# reverse_pol_protection.net
KiCad netlist of a schematic drawn in Altium Designer
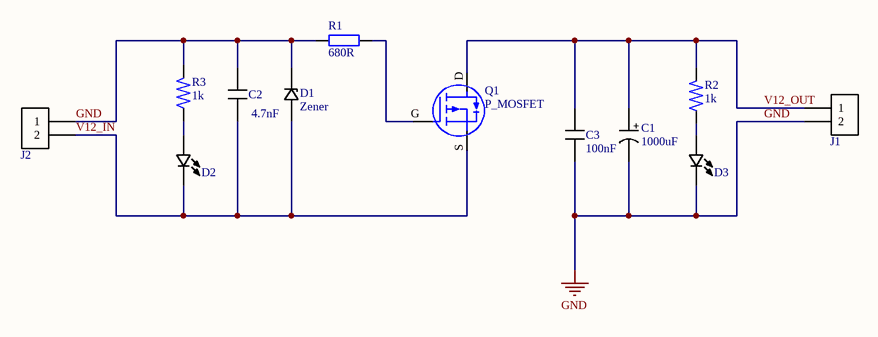
[diagram p0: reverse_pol_protection.SchDoc]

(export (version "E")
  (design (tool "Eeschema 10.0.6"))
  (components
    (comp (ref "C1")
      (value "1000uF")
      (footprint "RUBYCON_CAP_12.5x25")
      (description "Generic Electrolytic Capacitor")
      (libsource (lib "schematic_library") (part "Cap_Elec"))
    )
    (comp (ref "C2")
      (value "4.7nF")
      (footprint "YAGEO_CAP_0805_EA")
      (description "Generic Ceramic Capacitor")
      (libsource (lib "schematic_library") (part "Cap_Ceramic"))
    )
    (comp (ref "C3")
      (value "100nF")
      (footprint "YAGEO_CAP_0805_E0")
      (description "Generic Ceramic Capacitor")
      (libsource (lib "schematic_library") (part "Cap_Ceramic"))
    )
    (comp (ref "D1")
      (value "Zener")
      (footprint "NEXPERIA_DO-41")
      (description "Generic Zener Diode")
      (libsource (lib "intergrated_library") (part "Zener"))
    )
    (comp (ref "D2")
      (value "LED")
      (footprint "KINGBRIGHT_LED_THT_H4.9")
      (description "Generic Light Emitting Diode, Circuit indication")
      (libsource (lib "intergrated_library") (part "LED"))
    )
    (comp (ref "D3")
      (value "LED")
      (footprint "KINGBRIGHT_LED_THT_H4.9")
      (description "Generic Light Emitting Diode, Circuit indication")
      (libsource (lib "intergrated_library") (part "LED"))
    )
    (comp (ref "J1")
      (value "?")
      (footprint "KEFA_TERMINAL_2POS")
      (description "Generic 2 position terminal block")
      (libsource (lib "intergrated_library") (part "Terminal Block"))
    )
    (comp (ref "J2")
      (value "?")
      (footprint "KEFA_TERMINAL_2POS")
      (description "Generic 2 position terminal block")
      (libsource (lib "intergrated_library") (part "Terminal Block"))
    )
    (comp (ref "Q1")
      (value "P_MOSFET")
      (footprint "INFINEON_TO220-3")
      (description "Infineon P-Channel MOSFET")
      (libsource (lib "intergrated_library") (part "P_MOSFET"))
    )
    (comp (ref "R1")
      (value "680R")
      (footprint "YAGEO_RES_THT_P12.5")
      (description "Generic Resistor, Power > 1W")
      (libsource (lib "intergrated_library") (part "Resistor_L"))
    )
    (comp (ref "R2")
      (value "1k")
      (footprint "Yageo_RES_0805")
      (description "Generic Resistor, Power <= 1W")
      (libsource (lib "intergrated_library") (part "Resistor_S"))
    )
    (comp (ref "R3")
      (value "1k")
      (footprint "Yageo_RES_0805")
      (description "Generic Resistor, Power <= 1W")
      (libsource (lib "intergrated_library") (part "Resistor_S"))
    )
  )
  (nets
    (net (code "1") (name "/V12_IN") (class "Default")
      (node (ref "C2") (pin "1") (pintype "passive"))
      (node (ref "D1") (pin "A") (pinfunction "Anode_A") (pintype "passive"))
      (node (ref "D2") (pin "K") (pinfunction "Cathode_K") (pintype "passive"))
      (node (ref "J2") (pin "2") (pinfunction "2_2") (pintype "passive"))
      (node (ref "Q1") (pin "S") (pinfunction "Source_S") (pintype "passive"))
    )
    (net (code "2") (name "/V12_OUT") (class "Default")
      (node (ref "C1") (pin "1") (pintype "passive"))
      (node (ref "C3") (pin "2") (pintype "passive"))
      (node (ref "J1") (pin "1") (pinfunction "1_1") (pintype "passive"))
      (node (ref "Q1") (pin "D") (pinfunction "Drain_D") (pintype "passive"))
      (node (ref "R2") (pin "2") (pintype "passive"))
    )
    (net (code "3") (name "GND") (class "Default")
      (node (ref "C1") (pin "2") (pintype "passive"))
      (node (ref "C2") (pin "2") (pintype "passive"))
      (node (ref "C3") (pin "1") (pintype "passive"))
      (node (ref "D1") (pin "K") (pinfunction "Cathode_K") (pintype "passive"))
      (node (ref "D3") (pin "K") (pinfunction "Cathode_K") (pintype "passive"))
      (node (ref "J1") (pin "2") (pinfunction "2_2") (pintype "passive"))
      (node (ref "J2") (pin "1") (pinfunction "1_1") (pintype "passive"))
      (node (ref "R1") (pin "1") (pintype "passive"))
      (node (ref "R3") (pin "2") (pintype "passive"))
    )
    (net (code "4") (name "Net-(D2-Anode)") (class "Default")
      (node (ref "D2") (pin "A") (pinfunction "Anode_A") (pintype "passive"))
      (node (ref "R3") (pin "1") (pintype "passive"))
    )
    (net (code "5") (name "Net-(D3-Anode)") (class "Default")
      (node (ref "D3") (pin "A") (pinfunction "Anode_A") (pintype "passive"))
      (node (ref "R2") (pin "1") (pintype "passive"))
    )
    (net (code "6") (name "Net-(Q1-Gate)") (class "Default")
      (node (ref "Q1") (pin "G") (pinfunction "Gate_G") (pintype "passive"))
      (node (ref "R1") (pin "2") (pintype "passive"))
    )
  )
)
